# UI_Ticketing_Slave.net
KiCad netlist of a schematic drawn in Altium Designer
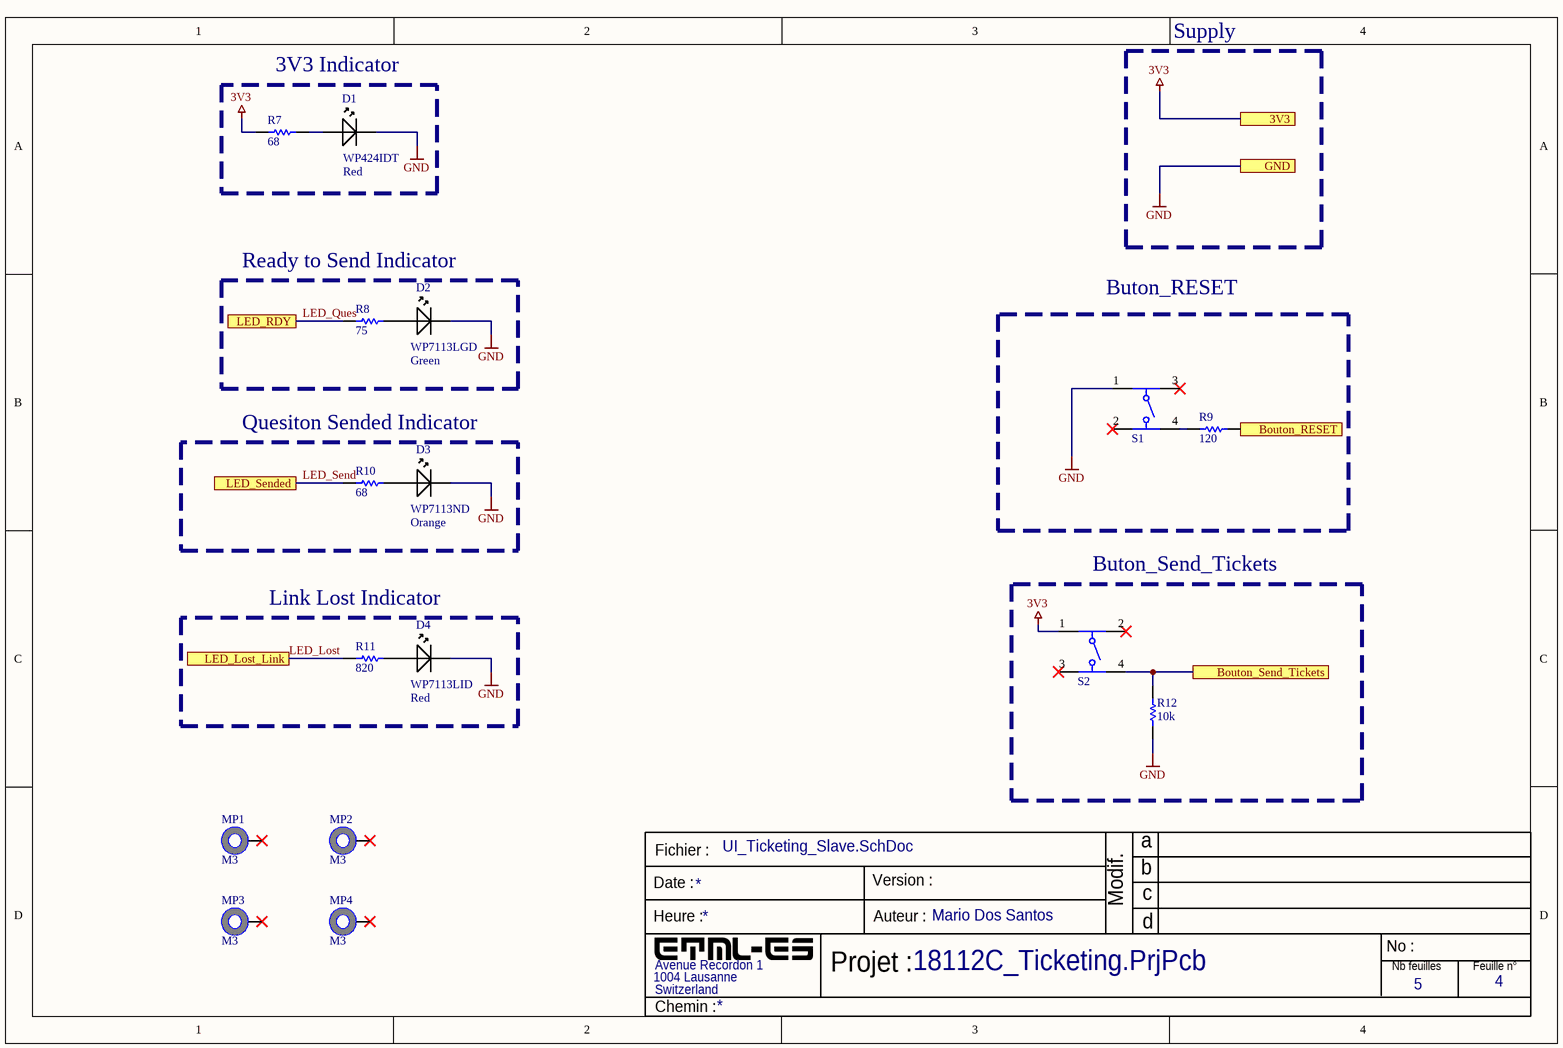
[diagram p0: UI_Ticketing_Slave.SchDoc]

(export (version "E")
  (design (tool "Eeschema 10.0.6"))
  (components
    (comp (ref "D1")
      (value "WP424IDT")
      (footprint "LED-2P-2.28-3MM")
      (description "LED")
      (fields (field (name "COLOR") "Red"))
      (libsource (lib "") (part "LED_1"))
    )
    (comp (ref "D2")
      (value "WP7113LGD")
      (footprint "Type 5mm")
      (description "LED")
      (fields (field (name "COLOR") "Green"))
      (libsource (lib "Spectrometre_Lib") (part "LED"))
    )
    (comp (ref "D3")
      (value "WP7113ND")
      (footprint "Type 5mm")
      (description "LED")
      (fields (field (name "COLOR") "Orange"))
      (libsource (lib "Spectrometre_Lib") (part "LED"))
    )
    (comp (ref "D4")
      (value "WP7113LID")
      (footprint "Type 5mm")
      (description "LED")
      (fields (field (name "COLOR") "Red"))
      (libsource (lib "Spectrometre_Lib") (part "LED"))
    )
    (comp (ref "MP1")
      (value "M3")
      (footprint "9774010151")
      (description "WA-SMSI SMT Steel Spacer, M2.5 Thread Internal, Length 1mm")
      (libsource (lib "ALTIUM-SMSI_SMT_STEEL_SPACER_M2_5_THREAD_INTERNAL-rev16b") (part "9774010151"))
    )
    (comp (ref "MP2")
      (value "M3")
      (footprint "9774010151")
      (description "WA-SMSI SMT Steel Spacer, M2.5 Thread Internal, Length 1mm")
      (libsource (lib "ALTIUM-SMSI_SMT_STEEL_SPACER_M2_5_THREAD_INTERNAL-rev16b") (part "9774010151"))
    )
    (comp (ref "MP3")
      (value "M3")
      (footprint "9774010151")
      (description "WA-SMSI SMT Steel Spacer, M2.5 Thread Internal, Length 1mm")
      (libsource (lib "ALTIUM-SMSI_SMT_STEEL_SPACER_M2_5_THREAD_INTERNAL-rev16b") (part "9774010151"))
    )
    (comp (ref "MP4")
      (value "M3")
      (footprint "9774010151")
      (description "WA-SMSI SMT Steel Spacer, M2.5 Thread Internal, Length 1mm")
      (libsource (lib "ALTIUM-SMSI_SMT_STEEL_SPACER_M2_5_THREAD_INTERNAL-rev16b") (part "9774010151"))
    )
    (comp (ref "R7")
      (value "68")
      (footprint "RESC0805(2012)_L")
      (description "100K 0.125W 5% 0805 (2012 Metric)  SMD")
      (libsource (lib "Altium Content Vault") (part "CMP-1013-00122-1"))
    )
    (comp (ref "R8")
      (value "75")
      (footprint "RESC0805(2012)_L")
      (description "100K 0.125W 5% 0805 (2012 Metric)  SMD")
      (libsource (lib "Altium Content Vault") (part "CMP-1013-00122-1"))
    )
    (comp (ref "R9")
      (value "120")
      (footprint "RESC0805(2012)_L")
      (description "100K 0.125W 5% 0805 (2012 Metric)  SMD")
      (libsource (lib "Altium Content Vault") (part "CMP-1013-00122-1"))
    )
    (comp (ref "R10")
      (value "68")
      (footprint "RESC0805(2012)_L")
      (description "100K 0.125W 5% 0805 (2012 Metric)  SMD")
      (libsource (lib "Altium Content Vault") (part "CMP-1013-00122-1"))
    )
    (comp (ref "R11")
      (value "820")
      (footprint "RESC0805(2012)_L")
      (description "100K 0.125W 5% 0805 (2012 Metric)  SMD")
      (libsource (lib "Altium Content Vault") (part "CMP-1013-00122-1"))
    )
    (comp (ref "R12")
      (value "10k")
      (footprint "RESC0805(2012)_L")
      (description "100K 0.125W 5% 0805 (2012 Metric)  SMD")
      (libsource (lib "Altium Content Vault") (part "CMP-1013-00122-1"))
    )
    (comp (ref "S1")
      (value "430182050816")
      (footprint "430182050816")
      (description "6x6mm SMD Tact Switch WS-TASV, height 5 mm, 160 gf")
      (libsource (lib "ALTIUM-WS-TASV-rev17b") (part "430182050816"))
    )
    (comp (ref "S2")
      (value "430466073726")
      (footprint "4304x60737x6_12x12x7.3")
      (description "WS-TATV 12x12mm washable Tact Switch, THT version")
      (libsource (lib "ALTIUM-WS-TATV-rev17a") (part "430466073726"))
    )
  )
  (nets
    (net (code "1") (name "/Bouton_RESET") (class "Default")
      (node (ref "R9") (pin "2") (pinfunction "2_2") (pintype "passive"))
    )
    (net (code "2") (name "/Bouton_Send_Tickets") (class "Default")
      (node (ref "R12") (pin "1") (pinfunction "1_1") (pintype "passive"))
      (node (ref "S2") (pin "4") (pinfunction "4_4") (pintype "passive"))
    )
    (net (code "3") (name "/LED_Lost") (class "Default")
      (node (ref "R11") (pin "2") (pinfunction "2_2") (pintype "passive"))
    )
    (net (code "4") (name "/LED_Ques") (class "Default")
      (node (ref "R8") (pin "2") (pinfunction "2_2") (pintype "passive"))
    )
    (net (code "5") (name "/LED_Send") (class "Default")
      (node (ref "R10") (pin "2") (pinfunction "2_2") (pintype "passive"))
    )
    (net (code "6") (name "3V3") (class "Default")
      (node (ref "R7") (pin "2") (pinfunction "2_2") (pintype "passive"))
      (node (ref "S2") (pin "1") (pinfunction "1_1") (pintype "passive"))
    )
    (net (code "7") (name "GND") (class "Default")
      (node (ref "D1") (pin "2") (pinfunction "Cathode_2") (pintype "passive"))
      (node (ref "D2") (pin "1") (pinfunction "Cathode_1") (pintype "passive"))
      (node (ref "D3") (pin "1") (pinfunction "Cathode_1") (pintype "passive"))
      (node (ref "D4") (pin "1") (pinfunction "Cathode_1") (pintype "passive"))
      (node (ref "R12") (pin "2") (pinfunction "2_2") (pintype "passive"))
      (node (ref "S1") (pin "1") (pinfunction "1_1") (pintype "passive"))
    )
    (net (code "8") (name "Net-(D1-Anode)") (class "Default")
      (node (ref "D1") (pin "1") (pinfunction "Anode_1") (pintype "passive"))
      (node (ref "R7") (pin "1") (pinfunction "1_1") (pintype "passive"))
    )
    (net (code "9") (name "Net-(D2-Anode)") (class "Default")
      (node (ref "D2") (pin "2") (pinfunction "Anode_2") (pintype "passive"))
      (node (ref "R8") (pin "1") (pinfunction "1_1") (pintype "passive"))
    )
    (net (code "10") (name "Net-(D3-Anode)") (class "Default")
      (node (ref "D3") (pin "2") (pinfunction "Anode_2") (pintype "passive"))
      (node (ref "R10") (pin "1") (pinfunction "1_1") (pintype "passive"))
    )
    (net (code "11") (name "Net-(D4-Anode)") (class "Default")
      (node (ref "D4") (pin "2") (pinfunction "Anode_2") (pintype "passive"))
      (node (ref "R11") (pin "1") (pinfunction "1_1") (pintype "passive"))
    )
    (net (code "12") (name "Net-(R9-Pad1)") (class "Default")
      (node (ref "R9") (pin "1") (pinfunction "1_1") (pintype "passive"))
      (node (ref "S1") (pin "4") (pinfunction "4_4") (pintype "passive"))
    )
    (net (code "13") (name "unconnected-(MP1-Pad1)") (class "Default")
      (node (ref "MP1") (pin "1") (pinfunction "1_1") (pintype "passive+no_connect"))
    )
    (net (code "14") (name "unconnected-(MP2-Pad1)") (class "Default")
      (node (ref "MP2") (pin "1") (pinfunction "1_1") (pintype "passive+no_connect"))
    )
    (net (code "15") (name "unconnected-(MP3-Pad1)") (class "Default")
      (node (ref "MP3") (pin "1") (pinfunction "1_1") (pintype "passive+no_connect"))
    )
    (net (code "16") (name "unconnected-(MP4-Pad1)") (class "Default")
      (node (ref "MP4") (pin "1") (pinfunction "1_1") (pintype "passive+no_connect"))
    )
    (net (code "17") (name "unconnected-(S1-Pad2)") (class "Default")
      (node (ref "S1") (pin "2") (pinfunction "2_2") (pintype "passive+no_connect"))
    )
    (net (code "18") (name "unconnected-(S1-Pad3)") (class "Default")
      (node (ref "S1") (pin "3") (pinfunction "3_3") (pintype "passive+no_connect"))
    )
    (net (code "19") (name "unconnected-(S2-Pad2)") (class "Default")
      (node (ref "S2") (pin "2") (pinfunction "2_2") (pintype "passive+no_connect"))
    )
    (net (code "20") (name "unconnected-(S2-Pad3)") (class "Default")
      (node (ref "S2") (pin "3") (pinfunction "3_3") (pintype "passive+no_connect"))
    )
  )
)
